# circuit.net
KiCad netlist of a schematic drawn in EAGLE
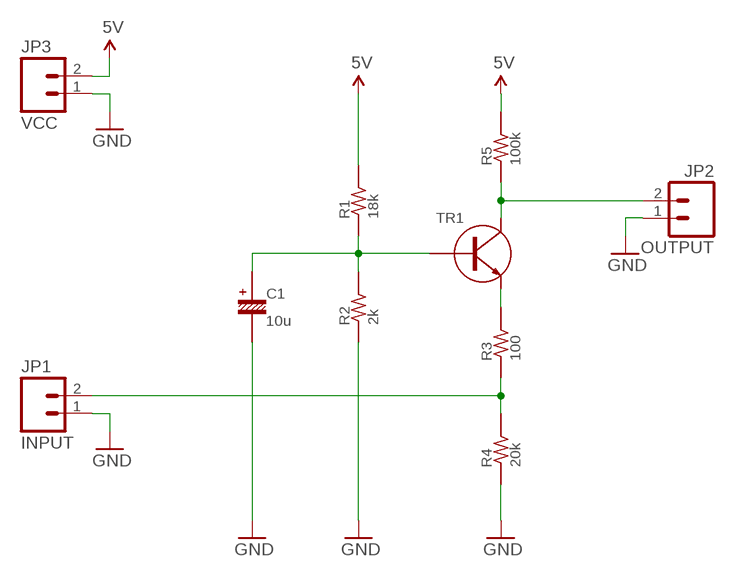
[diagram p0: schematic, sheet 1]

(export (version "E")
  (design (tool "Eeschema 10.0.6"))
  (components
    (comp (ref "C1")
      (value "10u")
      (footprint "eagle-import:16V-4-2.54")
      (libsource (lib "eagle-import") (part "CE-16V-04-2.54"))
    )
    (comp (ref "JP1")
      (value "INPUT")
      (footprint "eagle-import:1X02")
      (libsource (lib "eagle-import") (part "M02PTH"))
    )
    (comp (ref "JP2")
      (value "OUTPUT")
      (footprint "eagle-import:1X02")
      (libsource (lib "eagle-import") (part "M02PTH"))
    )
    (comp (ref "JP3")
      (value "VCC")
      (footprint "eagle-import:1X02")
      (libsource (lib "eagle-import") (part "M02PTH"))
    )
    (comp (ref "R1")
      (value "18k")
      (footprint "eagle-import:1_4W-7.62H")
      (libsource (lib "eagle-import") (part "R-1/4W-07.62"))
    )
    (comp (ref "R2")
      (value "2k")
      (footprint "eagle-import:1_4W-7.62H")
      (libsource (lib "eagle-import") (part "R-1/4W-07.62"))
    )
    (comp (ref "R3")
      (value "100")
      (footprint "eagle-import:1_4W-7.62H")
      (libsource (lib "eagle-import") (part "R-1/4W-07.62"))
    )
    (comp (ref "R4")
      (value "20k")
      (footprint "eagle-import:1_4W-7.62H")
      (libsource (lib "eagle-import") (part "R-1/4W-07.62"))
    )
    (comp (ref "R5")
      (value "100k")
      (footprint "eagle-import:1_4W-7.62H")
      (libsource (lib "eagle-import") (part "R-1/4W-07.62"))
    )
    (comp (ref "TR1")
      (value "TR-NPN-TO-92-ECB")
      (footprint "eagle-import:TO-92")
      (libsource (lib "eagle-import") (part "TR-NPN-TO-92-ECB"))
    )
  )
  (nets
    (net (code "1") (name "5V") (class "Default")
      (node (ref "JP3") (pin "2") (pinfunction "2_2") (pintype "passive"))
      (node (ref "R1") (pin "PAD2") (pinfunction "2_PAD2") (pintype "passive"))
      (node (ref "R5") (pin "PAD2") (pinfunction "2_PAD2") (pintype "passive"))
    )
    (net (code "2") (name "GND") (class "Default")
      (node (ref "C1") (pin "-") (pinfunction "-_-") (pintype "passive"))
      (node (ref "JP1") (pin "1") (pinfunction "1_1") (pintype "passive"))
      (node (ref "JP2") (pin "1") (pinfunction "1_1") (pintype "passive"))
      (node (ref "JP3") (pin "1") (pinfunction "1_1") (pintype "passive"))
      (node (ref "R2") (pin "PAD1") (pinfunction "1_PAD1") (pintype "passive"))
      (node (ref "R4") (pin "PAD1") (pinfunction "1_PAD1") (pintype "passive"))
    )
    (net (code "3") (name "Net-(R1-1)") (class "Default")
      (node (ref "C1") (pin "+") (pinfunction "+_+") (pintype "passive"))
      (node (ref "R1") (pin "PAD1") (pinfunction "1_PAD1") (pintype "passive"))
      (node (ref "R2") (pin "PAD2") (pinfunction "2_PAD2") (pintype "passive"))
      (node (ref "TR1") (pin "3") (pinfunction "B_3") (pintype "passive"))
    )
    (net (code "4") (name "Net-(R3-1)") (class "Default")
      (node (ref "JP1") (pin "2") (pinfunction "2_2") (pintype "passive"))
      (node (ref "R3") (pin "PAD1") (pinfunction "1_PAD1") (pintype "passive"))
      (node (ref "R4") (pin "PAD2") (pinfunction "2_PAD2") (pintype "passive"))
    )
    (net (code "5") (name "Net-(R3-2)") (class "Default")
      (node (ref "R3") (pin "PAD2") (pinfunction "2_PAD2") (pintype "passive"))
      (node (ref "TR1") (pin "1") (pinfunction "E_1") (pintype "passive"))
    )
    (net (code "6") (name "Net-(R5-1)") (class "Default")
      (node (ref "JP2") (pin "2") (pinfunction "2_2") (pintype "passive"))
      (node (ref "R5") (pin "PAD1") (pinfunction "1_PAD1") (pintype "passive"))
      (node (ref "TR1") (pin "2") (pinfunction "C_2") (pintype "passive"))
    )
  )
)
